# Relaya_the_second_Version_2.net
KiCad netlist of a schematic drawn in EAGLE
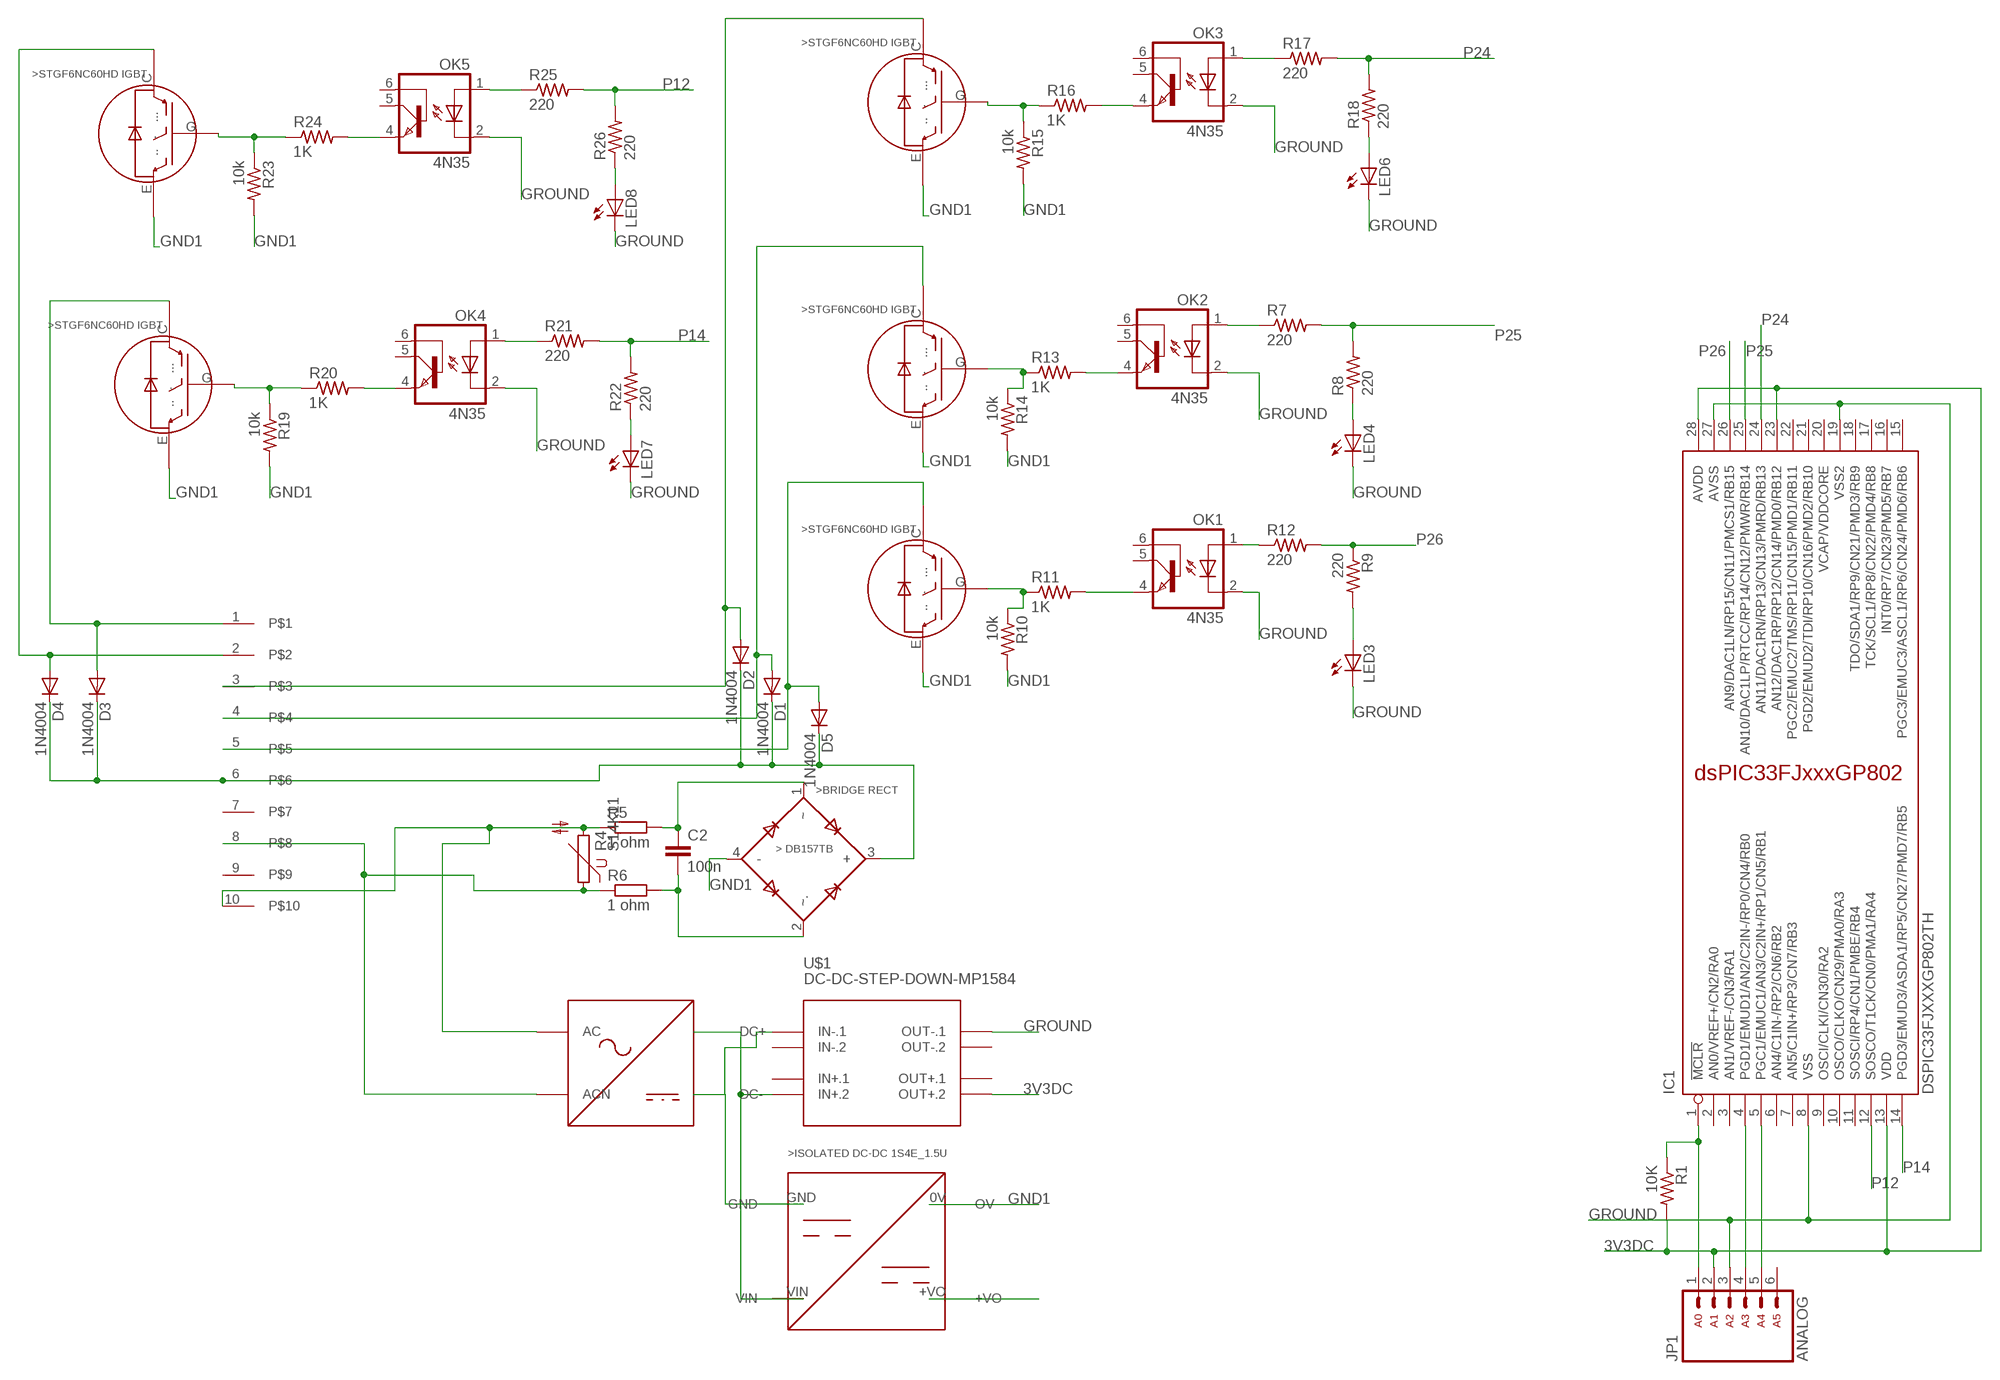
[diagram p0: schematic, sheet 1]

(export (version "E")
  (design (tool "Eeschema 10.0.6"))
  (components
    (comp (ref "ASD1")
      (value "MY_LIBRAY_RPD10W1S")
      (footprint "eagle-import:MY_LIBRAY_2343")
      (libsource (lib "eagle-import") (part "MY_LIBRAY_RPD10W1S"))
    )
    (comp (ref "C2")
      (value "100n")
      (footprint "eagle-import:C10B5")
      (libsource (lib "eagle-import") (part "C10/5"))
    )
    (comp (ref "D1")
      (value "1N4004")
      (footprint "eagle-import:DO41-10")
      (libsource (lib "eagle-import") (part "1N4004"))
    )
    (comp (ref "D2")
      (value "1N4004")
      (footprint "eagle-import:DO41-10")
      (libsource (lib "eagle-import") (part "1N4004"))
    )
    (comp (ref "D3")
      (value "1N4004")
      (footprint "eagle-import:DO41-10")
      (libsource (lib "eagle-import") (part "1N4004"))
    )
    (comp (ref "D4")
      (value "1N4004")
      (footprint "eagle-import:DO41-10")
      (libsource (lib "eagle-import") (part "1N4004"))
    )
    (comp (ref "D5")
      (value "1N4004")
      (footprint "eagle-import:DO41-10")
      (libsource (lib "eagle-import") (part "1N4004"))
    )
    (comp (ref "IC1")
      (value "DSPIC33FJXXXGP802TH")
      (footprint "eagle-import:DIL28-3")
      (libsource (lib "eagle-import") (part "DSPIC33FJXXXGP802TH"))
    )
    (comp (ref "JP1")
      (value "ARDUINO_CONN-ANALOGSIP")
      (footprint "eagle-import:CONN-1X06")
      (libsource (lib "eagle-import") (part "ARDUINO_CONN-ANALOGSIP"))
    )
    (comp (ref "LED3")
      (value "LED5MM")
      (footprint "eagle-import:LED5MM")
      (libsource (lib "eagle-import") (part "LED5MM"))
    )
    (comp (ref "LED4")
      (value "LED5MM")
      (footprint "eagle-import:LED5MM")
      (libsource (lib "eagle-import") (part "LED5MM"))
    )
    (comp (ref "LED6")
      (value "LED5MM")
      (footprint "eagle-import:LED5MM")
      (libsource (lib "eagle-import") (part "LED5MM"))
    )
    (comp (ref "LED7")
      (value "LED5MM")
      (footprint "eagle-import:LED5MM")
      (libsource (lib "eagle-import") (part "LED5MM"))
    )
    (comp (ref "LED8")
      (value "LED5MM")
      (footprint "eagle-import:LED5MM")
      (libsource (lib "eagle-import") (part "LED5MM"))
    )
    (comp (ref "OK1")
      (value "4N35")
      (footprint "eagle-import:DIL06")
      (fields (field (name "MF") "FAIRCHILD SEMICONDUCTOR"))
      (libsource (lib "eagle-import") (part "4N35"))
    )
    (comp (ref "OK2")
      (value "4N35")
      (footprint "eagle-import:DIL06")
      (fields (field (name "MF") "FAIRCHILD SEMICONDUCTOR"))
      (libsource (lib "eagle-import") (part "4N35"))
    )
    (comp (ref "OK3")
      (value "4N35")
      (footprint "eagle-import:DIL06")
      (fields (field (name "MF") "FAIRCHILD SEMICONDUCTOR"))
      (libsource (lib "eagle-import") (part "4N35"))
    )
    (comp (ref "OK4")
      (value "4N35")
      (footprint "eagle-import:DIL06")
      (fields (field (name "MF") "FAIRCHILD SEMICONDUCTOR"))
      (libsource (lib "eagle-import") (part "4N35"))
    )
    (comp (ref "OK5")
      (value "4N35")
      (footprint "eagle-import:DIL06")
      (fields (field (name "MF") "FAIRCHILD SEMICONDUCTOR"))
      (libsource (lib "eagle-import") (part "4N35"))
    )
    (comp (ref "R1")
      (value "10K")
      (footprint "eagle-import:0207_10")
      (libsource (lib "eagle-import") (part "R-US_0207/10"))
    )
    (comp (ref "R4")
      (value "S14K11")
      (footprint "eagle-import:S14K11")
      (libsource (lib "eagle-import") (part "S14K11"))
    )
    (comp (ref "R5")
      (value "1 ohm")
      (footprint "eagle-import:0617_17")
      (libsource (lib "eagle-import") (part "R-EU_0617/17"))
    )
    (comp (ref "R6")
      (value "1 ohm")
      (footprint "eagle-import:0617_17")
      (libsource (lib "eagle-import") (part "R-EU_0617/17"))
    )
    (comp (ref "R7")
      (value "220")
      (footprint "eagle-import:0207_10")
      (libsource (lib "eagle-import") (part "R-US_0207/10"))
    )
    (comp (ref "R8")
      (value "220")
      (footprint "eagle-import:0207_10")
      (libsource (lib "eagle-import") (part "R-US_0207/10"))
    )
    (comp (ref "R9")
      (value "220")
      (footprint "eagle-import:0207_10")
      (libsource (lib "eagle-import") (part "R-US_0207/10"))
    )
    (comp (ref "R10")
      (value "10k")
      (footprint "eagle-import:0207_10")
      (libsource (lib "eagle-import") (part "R-US_0207/10"))
    )
    (comp (ref "R11")
      (value "1K")
      (footprint "eagle-import:0207_10")
      (libsource (lib "eagle-import") (part "R-US_0207/10"))
    )
    (comp (ref "R12")
      (value "220")
      (footprint "eagle-import:0207_10")
      (libsource (lib "eagle-import") (part "R-US_0207/10"))
    )
    (comp (ref "R13")
      (value "1K")
      (footprint "eagle-import:0207_10")
      (libsource (lib "eagle-import") (part "R-US_0207/10"))
    )
    (comp (ref "R14")
      (value "10k")
      (footprint "eagle-import:0207_10")
      (libsource (lib "eagle-import") (part "R-US_0207/10"))
    )
    (comp (ref "R15")
      (value "10k")
      (footprint "eagle-import:0207_10")
      (libsource (lib "eagle-import") (part "R-US_0207/10"))
    )
    (comp (ref "R16")
      (value "1K")
      (footprint "eagle-import:0207_10")
      (libsource (lib "eagle-import") (part "R-US_0207/10"))
    )
    (comp (ref "R17")
      (value "220")
      (footprint "eagle-import:0207_10")
      (libsource (lib "eagle-import") (part "R-US_0207/10"))
    )
    (comp (ref "R18")
      (value "220")
      (footprint "eagle-import:0207_10")
      (libsource (lib "eagle-import") (part "R-US_0207/10"))
    )
    (comp (ref "R19")
      (value "10k")
      (footprint "eagle-import:0207_10")
      (libsource (lib "eagle-import") (part "R-US_0207/10"))
    )
    (comp (ref "R20")
      (value "1K")
      (footprint "eagle-import:0207_10")
      (libsource (lib "eagle-import") (part "R-US_0207/10"))
    )
    (comp (ref "R21")
      (value "220")
      (footprint "eagle-import:0207_10")
      (libsource (lib "eagle-import") (part "R-US_0207/10"))
    )
    (comp (ref "R22")
      (value "220")
      (footprint "eagle-import:0207_10")
      (libsource (lib "eagle-import") (part "R-US_0207/10"))
    )
    (comp (ref "R23")
      (value "10k")
      (footprint "eagle-import:0207_10")
      (libsource (lib "eagle-import") (part "R-US_0207/10"))
    )
    (comp (ref "R24")
      (value "1K")
      (footprint "eagle-import:0207_10")
      (libsource (lib "eagle-import") (part "R-US_0207/10"))
    )
    (comp (ref "R25")
      (value "220")
      (footprint "eagle-import:0207_10")
      (libsource (lib "eagle-import") (part "R-US_0207/10"))
    )
    (comp (ref "R26")
      (value "220")
      (footprint "eagle-import:0207_10")
      (libsource (lib "eagle-import") (part "R-US_0207/10"))
    )
    (comp (ref "U$1")
      (value "DC-DC-STEP-DOWN-MP1584")
      (footprint "eagle-import:DC-DC-STEP-DOWN-MP1584")
      (libsource (lib "eagle-import") (part "DC-DC-STEP-DOWN-MP1584"))
    )
    (comp (ref "U$2")
      (value "AIRSEP_POWER_CONNECTOR")
      (footprint "eagle-import:JST-XH-CONNECTORS-GHII_JST-XH-10-PACKAGE-ROUND-PAD")
      (libsource (lib "eagle-import") (part "AIRSEP_POWER_CONNECTOR"))
    )
    (comp (ref "U$3")
      (value "1S4E_1.5UA")
      (footprint "eagle-import:1S4E_1.5U")
      (libsource (lib "eagle-import") (part "1S4E_1.5UA"))
    )
    (comp (ref "U$4")
      (value "IGBT_STGF6NC60HDA")
      (footprint "eagle-import:STGF6NC60HD")
      (libsource (lib "eagle-import") (part "IGBT_STGF6NC60HDA"))
    )
    (comp (ref "U$5")
      (value "BRIDGE_RECT_DB157TBA")
      (footprint "eagle-import:DB157TB")
      (libsource (lib "eagle-import") (part "BRIDGE_RECT_DB157TBA"))
    )
    (comp (ref "U$6")
      (value "IGBT_STGF6NC60HDA")
      (footprint "eagle-import:STGF6NC60HD")
      (libsource (lib "eagle-import") (part "IGBT_STGF6NC60HDA"))
    )
    (comp (ref "U$7")
      (value "IGBT_STGF6NC60HDA")
      (footprint "eagle-import:STGF6NC60HD")
      (libsource (lib "eagle-import") (part "IGBT_STGF6NC60HDA"))
    )
    (comp (ref "U$8")
      (value "IGBT_STGF6NC60HDA")
      (footprint "eagle-import:STGF6NC60HD")
      (libsource (lib "eagle-import") (part "IGBT_STGF6NC60HDA"))
    )
    (comp (ref "U$9")
      (value "IGBT_STGF6NC60HDA")
      (footprint "eagle-import:STGF6NC60HD")
      (libsource (lib "eagle-import") (part "IGBT_STGF6NC60HDA"))
    )
  )
  (nets
    (net (code "1") (name "/3V3DC") (class "Default")
      (node (ref "IC1") (pin "13") (pinfunction "VDD_13") (pintype "power_in"))
      (node (ref "IC1") (pin "23") (pinfunction "AN12/DAC1RP/RP12/CN14/PMD0/RB12_23") (pintype "bidirectional"))
      (node (ref "IC1") (pin "28") (pinfunction "AVDD_28") (pintype "power_in"))
      (node (ref "JP1") (pin "2") (pinfunction "2_2") (pintype "passive"))
      (node (ref "R1") (pin "2") (pinfunction "2_2") (pintype "passive"))
      (node (ref "U$1") (pin "OUT+.2") (pinfunction "OUT+.2_OUT+.2") (pintype "bidirectional"))
    )
    (net (code "2") (name "/GND1") (class "Default")
      (node (ref "R10") (pin "2") (pinfunction "2_2") (pintype "passive"))
      (node (ref "R14") (pin "2") (pinfunction "2_2") (pintype "passive"))
      (node (ref "R15") (pin "2") (pinfunction "2_2") (pintype "passive"))
      (node (ref "R19") (pin "2") (pinfunction "2_2") (pintype "passive"))
      (node (ref "R23") (pin "2") (pinfunction "2_2") (pintype "passive"))
      (node (ref "U$3") (pin "0V") (pinfunction "OV_0V") (pintype "bidirectional"))
      (node (ref "U$4") (pin "E") (pinfunction ".._E") (pintype "bidirectional"))
      (node (ref "U$5") (pin "4") (pinfunction "-_4") (pintype "bidirectional"))
      (node (ref "U$6") (pin "E") (pinfunction ".._E") (pintype "bidirectional"))
      (node (ref "U$7") (pin "E") (pinfunction ".._E") (pintype "bidirectional"))
      (node (ref "U$8") (pin "E") (pinfunction ".._E") (pintype "bidirectional"))
      (node (ref "U$9") (pin "E") (pinfunction ".._E") (pintype "bidirectional"))
    )
    (net (code "3") (name "/GROUND") (class "Default")
      (node (ref "IC1") (pin "19") (pinfunction "VSS2_19") (pintype "power_in"))
      (node (ref "IC1") (pin "27") (pinfunction "AVSS_27") (pintype "power_in"))
      (node (ref "IC1") (pin "8") (pinfunction "VSS_8") (pintype "power_in"))
      (node (ref "JP1") (pin "3") (pinfunction "3_3") (pintype "passive"))
      (node (ref "LED3") (pin "K") (pinfunction "C_K") (pintype "passive"))
      (node (ref "LED4") (pin "K") (pinfunction "C_K") (pintype "passive"))
      (node (ref "LED6") (pin "K") (pinfunction "C_K") (pintype "passive"))
      (node (ref "LED7") (pin "K") (pinfunction "C_K") (pintype "passive"))
      (node (ref "LED8") (pin "K") (pinfunction "C_K") (pintype "passive"))
      (node (ref "OK1") (pin "2") (pinfunction "C_2") (pintype "passive"))
      (node (ref "OK2") (pin "2") (pinfunction "C_2") (pintype "passive"))
      (node (ref "OK3") (pin "2") (pinfunction "C_2") (pintype "passive"))
      (node (ref "OK4") (pin "2") (pinfunction "C_2") (pintype "passive"))
      (node (ref "OK5") (pin "2") (pinfunction "C_2") (pintype "passive"))
      (node (ref "U$1") (pin "OUT-.1") (pinfunction "OUT-.1_OUT-.1") (pintype "bidirectional"))
    )
    (net (code "4") (name "/P12") (class "Default")
      (node (ref "IC1") (pin "12") (pinfunction "SOSCO/T1CK/CN0/PMA1/RA4_12") (pintype "bidirectional"))
      (node (ref "R25") (pin "2") (pinfunction "2_2") (pintype "passive"))
      (node (ref "R26") (pin "2") (pinfunction "2_2") (pintype "passive"))
    )
    (net (code "5") (name "/P14") (class "Default")
      (node (ref "IC1") (pin "14") (pinfunction "PGD3/EMUD3/ASDA1/RP5/CN27/PMD7/RB5_14") (pintype "bidirectional"))
      (node (ref "R21") (pin "2") (pinfunction "2_2") (pintype "passive"))
      (node (ref "R22") (pin "2") (pinfunction "2_2") (pintype "passive"))
    )
    (net (code "6") (name "/P24") (class "Default")
      (node (ref "IC1") (pin "24") (pinfunction "AN11/DAC1RN/RP13/CN13/PMRD/RB13_24") (pintype "bidirectional"))
      (node (ref "R17") (pin "2") (pinfunction "2_2") (pintype "passive"))
      (node (ref "R18") (pin "2") (pinfunction "2_2") (pintype "passive"))
    )
    (net (code "7") (name "/P25") (class "Default")
      (node (ref "IC1") (pin "25") (pinfunction "AN10/DAC1LP/RTCC/RP14/CN12/PMWR/RB14_25") (pintype "bidirectional"))
      (node (ref "R7") (pin "2") (pinfunction "2_2") (pintype "passive"))
      (node (ref "R8") (pin "2") (pinfunction "2_2") (pintype "passive"))
    )
    (net (code "8") (name "/P26") (class "Default")
      (node (ref "IC1") (pin "26") (pinfunction "AN9/DAC1LN/RP15/CN11/PMCS1/RB15_26") (pintype "bidirectional"))
      (node (ref "R12") (pin "2") (pinfunction "2_2") (pintype "passive"))
      (node (ref "R9") (pin "1") (pinfunction "1_1") (pintype "passive"))
    )
    (net (code "9") (name "/VCAP{slash}VDDCORE") (class "Default")
      (node (ref "IC1") (pin "20") (pinfunction "VCAP/VDDCORE_20") (pintype "power_in"))
    )
    (net (code "10") (name "Net-(ASD1-PadDC+)") (class "Default")
      (node (ref "ASD1") (pin "DC+") (pinfunction "DC+_DC+") (pintype "bidirectional"))
      (node (ref "U$1") (pin "IN+.2") (pinfunction "IN+.2_IN+.2") (pintype "bidirectional"))
      (node (ref "U$3") (pin "VIN") (pinfunction "VIN_VIN") (pintype "bidirectional"))
    )
    (net (code "11") (name "Net-(ASD1-PadDC-)") (class "Default")
      (node (ref "ASD1") (pin "DC-") (pinfunction "DC-_DC-") (pintype "bidirectional"))
      (node (ref "U$1") (pin "IN-.1") (pinfunction "IN-.1_IN-.1") (pintype "bidirectional"))
      (node (ref "U$3") (pin "GND") (pinfunction "GND_GND") (pintype "bidirectional"))
    )
    (net (code "12") (name "Net-(IC1-PGC1{slash}EMUC1{slash}AN3{slash}C2IN+{slash}RP1{slash}CN5{slash}RB1)") (class "Default")
      (node (ref "IC1") (pin "5") (pinfunction "PGC1/EMUC1/AN3/C2IN+/RP1/CN5/RB1_5") (pintype "bidirectional"))
      (node (ref "JP1") (pin "5") (pinfunction "5_5") (pintype "passive"))
    )
    (net (code "13") (name "Net-(IC1-PGD1{slash}EMUD1{slash}AN2{slash}C2IN-{slash}RP0{slash}CN4{slash}RB0)") (class "Default")
      (node (ref "IC1") (pin "4") (pinfunction "PGD1/EMUD1/AN2/C2IN-/RP0/CN4/RB0_4") (pintype "bidirectional"))
      (node (ref "JP1") (pin "4") (pinfunction "4_4") (pintype "passive"))
    )
    (net (code "14") (name "Net-(IC1-~{MCLR})") (class "Default")
      (node (ref "IC1") (pin "1") (pinfunction "~{MCLR}_1") (pintype "input"))
      (node (ref "JP1") (pin "1") (pinfunction "1_1") (pintype "passive"))
      (node (ref "R1") (pin "1") (pinfunction "1_1") (pintype "passive"))
    )
    (net (code "15") (name "Net-(LED3-PadA)") (class "Default")
      (node (ref "LED3") (pin "A") (pinfunction "A_A") (pintype "passive"))
      (node (ref "R9") (pin "2") (pinfunction "2_2") (pintype "passive"))
    )
    (net (code "16") (name "Net-(LED4-PadA)") (class "Default")
      (node (ref "LED4") (pin "A") (pinfunction "A_A") (pintype "passive"))
      (node (ref "R8") (pin "1") (pinfunction "1_1") (pintype "passive"))
    )
    (net (code "17") (name "Net-(LED6-PadA)") (class "Default")
      (node (ref "LED6") (pin "A") (pinfunction "A_A") (pintype "passive"))
      (node (ref "R18") (pin "1") (pinfunction "1_1") (pintype "passive"))
    )
    (net (code "18") (name "Net-(LED7-PadA)") (class "Default")
      (node (ref "LED7") (pin "A") (pinfunction "A_A") (pintype "passive"))
      (node (ref "R22") (pin "1") (pinfunction "1_1") (pintype "passive"))
    )
    (net (code "19") (name "Net-(LED8-PadA)") (class "Default")
      (node (ref "LED8") (pin "A") (pinfunction "A_A") (pintype "passive"))
      (node (ref "R26") (pin "1") (pinfunction "1_1") (pintype "passive"))
    )
    (net (code "20") (name "Net-(OK1-A)") (class "Default")
      (node (ref "OK1") (pin "1") (pinfunction "A_1") (pintype "passive"))
      (node (ref "R12") (pin "1") (pinfunction "1_1") (pintype "passive"))
    )
    (net (code "21") (name "Net-(OK1-EMI)") (class "Default")
      (node (ref "OK1") (pin "4") (pinfunction "EMI_4") (pintype "passive"))
      (node (ref "R11") (pin "2") (pinfunction "2_2") (pintype "passive"))
    )
    (net (code "22") (name "Net-(OK2-A)") (class "Default")
      (node (ref "OK2") (pin "1") (pinfunction "A_1") (pintype "passive"))
      (node (ref "R7") (pin "1") (pinfunction "1_1") (pintype "passive"))
    )
    (net (code "23") (name "Net-(OK2-EMI)") (class "Default")
      (node (ref "OK2") (pin "4") (pinfunction "EMI_4") (pintype "passive"))
      (node (ref "R13") (pin "2") (pinfunction "2_2") (pintype "passive"))
    )
    (net (code "24") (name "Net-(OK3-A)") (class "Default")
      (node (ref "OK3") (pin "1") (pinfunction "A_1") (pintype "passive"))
      (node (ref "R17") (pin "1") (pinfunction "1_1") (pintype "passive"))
    )
    (net (code "25") (name "Net-(OK3-EMI)") (class "Default")
      (node (ref "OK3") (pin "4") (pinfunction "EMI_4") (pintype "passive"))
      (node (ref "R16") (pin "2") (pinfunction "2_2") (pintype "passive"))
    )
    (net (code "26") (name "Net-(OK4-A)") (class "Default")
      (node (ref "OK4") (pin "1") (pinfunction "A_1") (pintype "passive"))
      (node (ref "R21") (pin "1") (pinfunction "1_1") (pintype "passive"))
    )
    (net (code "27") (name "Net-(OK4-EMI)") (class "Default")
      (node (ref "OK4") (pin "4") (pinfunction "EMI_4") (pintype "passive"))
      (node (ref "R20") (pin "2") (pinfunction "2_2") (pintype "passive"))
    )
    (net (code "28") (name "Net-(OK5-A)") (class "Default")
      (node (ref "OK5") (pin "1") (pinfunction "A_1") (pintype "passive"))
      (node (ref "R25") (pin "1") (pinfunction "1_1") (pintype "passive"))
    )
    (net (code "29") (name "Net-(OK5-EMI)") (class "Default")
      (node (ref "OK5") (pin "4") (pinfunction "EMI_4") (pintype "passive"))
      (node (ref "R24") (pin "2") (pinfunction "2_2") (pintype "passive"))
    )
    (net (code "30") (name "Net-(U$2-P$1)") (class "Default")
      (node (ref "D3") (pin "A") (pinfunction "A_A") (pintype "passive"))
      (node (ref "U$2") (pin "1") (pinfunction "P$1_1") (pintype "bidirectional"))
      (node (ref "U$8") (pin "C") (pinfunction "..._C") (pintype "bidirectional"))
    )
    (net (code "31") (name "Net-(U$2-P$2)") (class "Default")
      (node (ref "D4") (pin "A") (pinfunction "A_A") (pintype "passive"))
      (node (ref "U$2") (pin "2") (pinfunction "P$2_2") (pintype "bidirectional"))
      (node (ref "U$9") (pin "C") (pinfunction "..._C") (pintype "bidirectional"))
    )
    (net (code "32") (name "Net-(U$2-P$3)") (class "Default")
      (node (ref "D2") (pin "A") (pinfunction "A_A") (pintype "passive"))
      (node (ref "U$2") (pin "3") (pinfunction "P$3_3") (pintype "bidirectional"))
      (node (ref "U$7") (pin "C") (pinfunction "..._C") (pintype "bidirectional"))
    )
    (net (code "33") (name "Net-(U$2-P$4)") (class "Default")
      (node (ref "D1") (pin "A") (pinfunction "A_A") (pintype "passive"))
      (node (ref "U$2") (pin "4") (pinfunction "P$4_4") (pintype "bidirectional"))
      (node (ref "U$6") (pin "C") (pinfunction "..._C") (pintype "bidirectional"))
    )
    (net (code "34") (name "Net-(U$2-P$5)") (class "Default")
      (node (ref "D5") (pin "A") (pinfunction "A_A") (pintype "passive"))
      (node (ref "U$2") (pin "5") (pinfunction "P$5_5") (pintype "bidirectional"))
      (node (ref "U$4") (pin "C") (pinfunction "..._C") (pintype "bidirectional"))
    )
    (net (code "35") (name "Net-(U$2-P$6)") (class "Default")
      (node (ref "D1") (pin "C") (pinfunction "C_C") (pintype "passive"))
      (node (ref "D2") (pin "C") (pinfunction "C_C") (pintype "passive"))
      (node (ref "D3") (pin "C") (pinfunction "C_C") (pintype "passive"))
      (node (ref "D4") (pin "C") (pinfunction "C_C") (pintype "passive"))
      (node (ref "D5") (pin "C") (pinfunction "C_C") (pintype "passive"))
      (node (ref "U$2") (pin "6") (pinfunction "P$6_6") (pintype "bidirectional"))
      (node (ref "U$5") (pin "3") (pinfunction "+_3") (pintype "bidirectional"))
    )
    (net (code "36") (name "Net-(U$2-P$8)") (class "Default")
      (node (ref "ASD1") (pin "ACN") (pinfunction "ACN_ACN") (pintype "bidirectional"))
      (node (ref "R4") (pin "1") (pinfunction "1_1") (pintype "passive"))
      (node (ref "R6") (pin "1") (pinfunction "1_1") (pintype "passive"))
      (node (ref "U$2") (pin "8") (pinfunction "P$8_8") (pintype "bidirectional"))
    )
    (net (code "37") (name "Net-(U$2-P$10)") (class "Default")
      (node (ref "ASD1") (pin "AC") (pinfunction "AC_AC") (pintype "bidirectional"))
      (node (ref "R4") (pin "2") (pinfunction "2_2") (pintype "passive"))
      (node (ref "R5") (pin "1") (pinfunction "1_1") (pintype "passive"))
      (node (ref "U$2") (pin "10") (pinfunction "P$10_10") (pintype "bidirectional"))
    )
    (net (code "38") (name "Net-(U$4-.)") (class "Default")
      (node (ref "R10") (pin "1") (pinfunction "1_1") (pintype "passive"))
      (node (ref "R11") (pin "1") (pinfunction "1_1") (pintype "passive"))
      (node (ref "U$4") (pin "G") (pinfunction "._G") (pintype "bidirectional"))
    )
    (net (code "39") (name "Net-(U$5-~)") (class "Default")
      (node (ref "C2") (pin "1") (pinfunction "1_1") (pintype "passive"))
      (node (ref "R5") (pin "2") (pinfunction "2_2") (pintype "passive"))
      (node (ref "U$5") (pin "1") (pinfunction "~_1") (pintype "bidirectional"))
    )
    (net (code "40") (name "Net-(U$5-~{.})") (class "Default")
      (node (ref "C2") (pin "2") (pinfunction "2_2") (pintype "passive"))
      (node (ref "R6") (pin "2") (pinfunction "2_2") (pintype "passive"))
      (node (ref "U$5") (pin "2") (pinfunction "~{.}_2") (pintype "bidirectional"))
    )
    (net (code "41") (name "Net-(U$6-.)") (class "Default")
      (node (ref "R13") (pin "1") (pinfunction "1_1") (pintype "passive"))
      (node (ref "R14") (pin "1") (pinfunction "1_1") (pintype "passive"))
      (node (ref "U$6") (pin "G") (pinfunction "._G") (pintype "bidirectional"))
    )
    (net (code "42") (name "Net-(U$7-.)") (class "Default")
      (node (ref "R15") (pin "1") (pinfunction "1_1") (pintype "passive"))
      (node (ref "R16") (pin "1") (pinfunction "1_1") (pintype "passive"))
      (node (ref "U$7") (pin "G") (pinfunction "._G") (pintype "bidirectional"))
    )
    (net (code "43") (name "Net-(U$8-.)") (class "Default")
      (node (ref "R19") (pin "1") (pinfunction "1_1") (pintype "passive"))
      (node (ref "R20") (pin "1") (pinfunction "1_1") (pintype "passive"))
      (node (ref "U$8") (pin "G") (pinfunction "._G") (pintype "bidirectional"))
    )
    (net (code "44") (name "Net-(U$9-.)") (class "Default")
      (node (ref "R23") (pin "1") (pinfunction "1_1") (pintype "passive"))
      (node (ref "R24") (pin "1") (pinfunction "1_1") (pintype "passive"))
      (node (ref "U$9") (pin "G") (pinfunction "._G") (pintype "bidirectional"))
    )
    (net (code "45") (name "unconnected-(IC1-AN0{slash}VREF+{slash}CN2{slash}RA0-Pad2)") (class "Default")
      (node (ref "IC1") (pin "2") (pinfunction "AN0/VREF+/CN2/RA0_2") (pintype "bidirectional"))
    )
    (net (code "46") (name "unconnected-(IC1-AN1{slash}VREF-{slash}CN3{slash}RA1-Pad3)") (class "Default")
      (node (ref "IC1") (pin "3") (pinfunction "AN1/VREF-/CN3/RA1_3") (pintype "bidirectional"))
    )
    (net (code "47") (name "unconnected-(IC1-AN4{slash}C1IN-{slash}RP2{slash}CN6{slash}RB2-Pad6)") (class "Default")
      (node (ref "IC1") (pin "6") (pinfunction "AN4/C1IN-/RP2/CN6/RB2_6") (pintype "bidirectional"))
    )
    (net (code "48") (name "unconnected-(IC1-AN5{slash}C1IN+{slash}RP3{slash}CN7{slash}RB3-Pad7)") (class "Default")
      (node (ref "IC1") (pin "7") (pinfunction "AN5/C1IN+/RP3/CN7/RB3_7") (pintype "bidirectional"))
    )
    (net (code "49") (name "unconnected-(IC1-INT0{slash}RP7{slash}CN23{slash}PMD5{slash}RB7-Pad16)") (class "Default")
      (node (ref "IC1") (pin "16") (pinfunction "INT0/RP7/CN23/PMD5/RB7_16") (pintype "bidirectional"))
    )
    (net (code "50") (name "unconnected-(IC1-OSCI{slash}CLKI{slash}CN30{slash}RA2-Pad9)") (class "Default")
      (node (ref "IC1") (pin "9") (pinfunction "OSCI/CLKI/CN30/RA2_9") (pintype "bidirectional"))
    )
    (net (code "51") (name "unconnected-(IC1-OSCO{slash}CLKO{slash}CN29{slash}PMA0{slash}RA3-Pad10)") (class "Default")
      (node (ref "IC1") (pin "10") (pinfunction "OSCO/CLKO/CN29/PMA0/RA3_10") (pintype "bidirectional"))
    )
    (net (code "52") (name "unconnected-(IC1-PGC2{slash}EMUC2{slash}TMS{slash}RP11{slash}CN15{slash}PMD1{slash}RB11-Pad22)") (class "Default")
      (node (ref "IC1") (pin "22") (pinfunction "PGC2/EMUC2/TMS/RP11/CN15/PMD1/RB11_22") (pintype "bidirectional"))
    )
    (net (code "53") (name "unconnected-(IC1-PGC3{slash}EMUC3{slash}ASCL1{slash}RP6{slash}CN24{slash}PMD6{slash}RB6-Pad15)") (class "Default")
      (node (ref "IC1") (pin "15") (pinfunction "PGC3/EMUC3/ASCL1/RP6/CN24/PMD6/RB6_15") (pintype "bidirectional"))
    )
    (net (code "54") (name "unconnected-(IC1-PGD2{slash}EMUD2{slash}TDI{slash}RP10{slash}CN16{slash}PMD2{slash}RB10-Pad21)") (class "Default")
      (node (ref "IC1") (pin "21") (pinfunction "PGD2/EMUD2/TDI/RP10/CN16/PMD2/RB10_21") (pintype "bidirectional"))
    )
    (net (code "55") (name "unconnected-(IC1-SOSCI{slash}RP4{slash}CN1{slash}PMBE{slash}RB4-Pad11)") (class "Default")
      (node (ref "IC1") (pin "11") (pinfunction "SOSCI/RP4/CN1/PMBE/RB4_11") (pintype "bidirectional"))
    )
    (net (code "56") (name "unconnected-(IC1-TCK{slash}SCL1{slash}RP8{slash}CN22{slash}PMD4{slash}RB8-Pad17)") (class "Default")
      (node (ref "IC1") (pin "17") (pinfunction "TCK/SCL1/RP8/CN22/PMD4/RB8_17") (pintype "bidirectional"))
    )
    (net (code "57") (name "unconnected-(IC1-TDO{slash}SDA1{slash}RP9{slash}CN21{slash}PMD3{slash}RB9-Pad18)") (class "Default")
      (node (ref "IC1") (pin "18") (pinfunction "TDO/SDA1/RP9/CN21/PMD3/RB9_18") (pintype "bidirectional"))
    )
    (net (code "58") (name "unconnected-(JP1-Pad6)") (class "Default")
      (node (ref "JP1") (pin "6") (pinfunction "6_6") (pintype "passive"))
    )
    (net (code "59") (name "unconnected-(OK1-BAS-Pad6)") (class "Default")
      (node (ref "OK1") (pin "6") (pinfunction "BAS_6") (pintype "passive"))
    )
    (net (code "60") (name "unconnected-(OK1-COL-Pad5)") (class "Default")
      (node (ref "OK1") (pin "5") (pinfunction "COL_5") (pintype "passive"))
    )
    (net (code "61") (name "unconnected-(OK2-BAS-Pad6)") (class "Default")
      (node (ref "OK2") (pin "6") (pinfunction "BAS_6") (pintype "passive"))
    )
    (net (code "62") (name "unconnected-(OK2-COL-Pad5)") (class "Default")
      (node (ref "OK2") (pin "5") (pinfunction "COL_5") (pintype "passive"))
    )
    (net (code "63") (name "unconnected-(OK3-BAS-Pad6)") (class "Default")
      (node (ref "OK3") (pin "6") (pinfunction "BAS_6") (pintype "passive"))
    )
    (net (code "64") (name "unconnected-(OK3-COL-Pad5)") (class "Default")
      (node (ref "OK3") (pin "5") (pinfunction "COL_5") (pintype "passive"))
    )
    (net (code "65") (name "unconnected-(OK4-BAS-Pad6)") (class "Default")
      (node (ref "OK4") (pin "6") (pinfunction "BAS_6") (pintype "passive"))
    )
    (net (code "66") (name "unconnected-(OK4-COL-Pad5)") (class "Default")
      (node (ref "OK4") (pin "5") (pinfunction "COL_5") (pintype "passive"))
    )
    (net (code "67") (name "unconnected-(OK5-BAS-Pad6)") (class "Default")
      (node (ref "OK5") (pin "6") (pinfunction "BAS_6") (pintype "passive"))
    )
    (net (code "68") (name "unconnected-(OK5-COL-Pad5)") (class "Default")
      (node (ref "OK5") (pin "5") (pinfunction "COL_5") (pintype "passive"))
    )
    (net (code "69") (name "unconnected-(U$1-PadIN+.1)") (class "Default")
      (node (ref "U$1") (pin "IN+.1") (pinfunction "IN+.1_IN+.1") (pintype "bidirectional"))
    )
    (net (code "70") (name "unconnected-(U$1-PadIN-.2)") (class "Default")
      (node (ref "U$1") (pin "IN-.2") (pinfunction "IN-.2_IN-.2") (pintype "bidirectional"))
    )
    (net (code "71") (name "unconnected-(U$1-PadOUT+.1)") (class "Default")
      (node (ref "U$1") (pin "OUT+.1") (pinfunction "OUT+.1_OUT+.1") (pintype "bidirectional"))
    )
    (net (code "72") (name "unconnected-(U$1-PadOUT-.2)") (class "Default")
      (node (ref "U$1") (pin "OUT-.2") (pinfunction "OUT-.2_OUT-.2") (pintype "bidirectional"))
    )
    (net (code "73") (name "unconnected-(U$2-P$7-Pad7)") (class "Default")
      (node (ref "U$2") (pin "7") (pinfunction "P$7_7") (pintype "bidirectional"))
    )
    (net (code "74") (name "unconnected-(U$2-P$9-Pad9)") (class "Default")
      (node (ref "U$2") (pin "9") (pinfunction "P$9_9") (pintype "bidirectional"))
    )
    (net (code "75") (name "unconnected-(U$3-Pad+VO)") (class "Default")
      (node (ref "U$3") (pin "+VO") (pinfunction "+VO_+VO") (pintype "bidirectional"))
    )
  )
)
